# STM32f103RBT6.net
KiCad netlist of a schematic drawn in Altium Designer
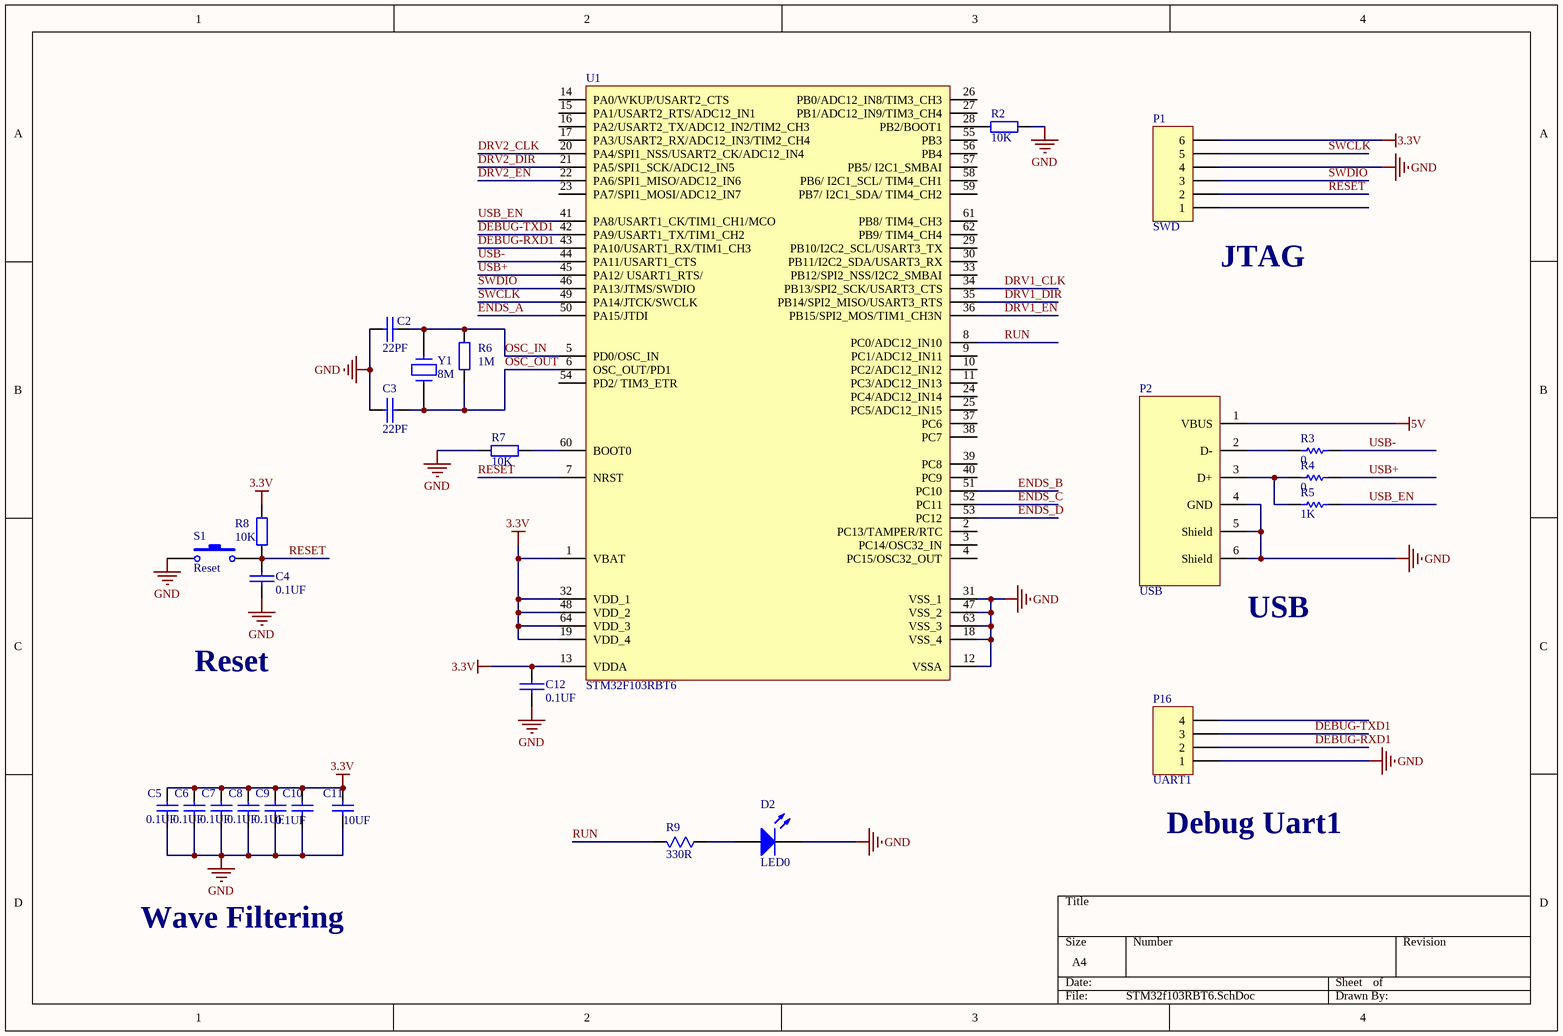
[diagram p0: STM32f103RBT6.SchDoc]

(export (version "E")
  (design (tool "Eeschema 10.0.6"))
  (components
    (comp (ref "C2")
      (value "22PF")
      (footprint "0603(1608)")
      (description "Capacitor")
      (libsource (lib "*") (part "CAP"))
    )
    (comp (ref "C3")
      (value "22PF")
      (footprint "0603(1608)")
      (description "Capacitor")
      (libsource (lib "*") (part "CAP"))
    )
    (comp (ref "C4")
      (value "0.1UF")
      (footprint "0603(1608)")
      (description "Capacitor")
      (libsource (lib "*") (part "CAP"))
    )
    (comp (ref "C5")
      (value "0.1UF")
      (footprint "0603(1608)")
      (description "Capacitor")
      (fields (field (name "PUBLISHER") "Altium Limited"))
      (libsource (lib "*") (part "Cap"))
    )
    (comp (ref "C6")
      (value "0.1UF")
      (footprint "0603(1608)")
      (description "Capacitor")
      (fields (field (name "PUBLISHER") "Altium Limited"))
      (libsource (lib "*") (part "Cap"))
    )
    (comp (ref "C7")
      (value "0.1UF")
      (footprint "0603(1608)")
      (description "Capacitor")
      (fields (field (name "PUBLISHER") "Altium Limited"))
      (libsource (lib "*") (part "Cap"))
    )
    (comp (ref "C8")
      (value "0.1UF")
      (footprint "0603(1608)")
      (description "Capacitor")
      (fields (field (name "PUBLISHER") "Altium Limited"))
      (libsource (lib "*") (part "Cap"))
    )
    (comp (ref "C9")
      (value "0.1UF")
      (footprint "0603(1608)")
      (description "Capacitor")
      (fields (field (name "PUBLISHER") "Altium Limited"))
      (libsource (lib "*") (part "Cap"))
    )
    (comp (ref "C10")
      (value "0.1UF")
      (footprint "0603(1608)")
      (description "Capacitor")
      (fields (field (name "PUBLISHER") "Altium Limited"))
      (libsource (lib "*") (part "Cap"))
    )
    (comp (ref "C11")
      (value "10UF")
      (footprint "0805(2012)")
      (description "Capacitor")
      (fields (field (name "PUBLISHER") "Altium Limited"))
      (libsource (lib "*") (part "Cap"))
    )
    (comp (ref "C12")
      (value "0.1UF")
      (footprint "0603(1608)")
      (description "Capacitor")
      (libsource (lib "*") (part "CAP"))
    )
    (comp (ref "D2")
      (value "LED0")
      (footprint "LED")
      (description "Typical INFRARED GaAs LED")
      (fields (field (name "PUBLISHER") "Altium Limited"))
      (libsource (lib "Miscellaneous Devices") (part "LED0"))
    )
    (comp (ref "P1")
      (value "SWD")
      (footprint "HDR1X6")
      (description "Header, 6-Pin")
      (fields (field (name "PUBLISHER") "Altium Limited"))
      (libsource (lib "Miscellaneous Connectors") (part "Header 6"))
    )
    (comp (ref "P2") (value "USB") (footprint "USB/SM0.8-6H5") (libsource (lib "Schlib_ZG") (part "Con Usb")))
    (comp (ref "P16")
      (value "UART1")
      (footprint "HDR1X4")
      (description "Header, 4-Pin")
      (fields (field (name "PUBLISHER") "Altium Limited"))
      (libsource (lib "Miscellaneous Connectors") (part "Header 4"))
    )
    (comp (ref "R2")
      (value "10K")
      (footprint "0603(1608)")
      (description "Resistor")
      (libsource (lib "Miscellaneous Devices") (part "Res2"))
    )
    (comp (ref "R3")
      (value "0")
      (footprint "0603(1608)")
      (description "Semiconductor Resistor")
      (fields (field (name "PUBLISHER") "Altium Limited"))
      (libsource (lib "Miscellaneous Devices") (part "Res Semi"))
    )
    (comp (ref "R4")
      (value "0")
      (footprint "0603(1608)")
      (description "Semiconductor Resistor")
      (fields (field (name "PUBLISHER") "Altium Limited"))
      (libsource (lib "Miscellaneous Devices") (part "Res Semi"))
    )
    (comp (ref "R5")
      (value "1K")
      (footprint "0603(1608)")
      (description "Semiconductor Resistor")
      (fields (field (name "PUBLISHER") "Altium Limited"))
      (libsource (lib "Miscellaneous Devices") (part "Res Semi"))
    )
    (comp (ref "R6")
      (value "1M")
      (footprint "0603(1608)")
      (description "Resistor")
      (libsource (lib "") (part "Res2_1"))
    )
    (comp (ref "R7")
      (value "10K")
      (footprint "0603(1608)")
      (description "Resistor")
      (libsource (lib "Miscellaneous Devices") (part "Res2"))
    )
    (comp (ref "R8")
      (value "10K")
      (footprint "0603(1608)")
      (description "Resistor")
      (libsource (lib "") (part "Res2_1"))
    )
    (comp (ref "R9") (value "330R") (footprint "0603(1608)") (libsource (lib "YT1_SCH_99SE") (part "RES")))
    (comp (ref "S1")
      (value "Reset")
      (footprint "SW-6")
      (description "Switch")
      (fields (field (name "PUBLISHER") "Altium Limited"))
      (libsource (lib "Schlib_ZG") (part "SW-PB"))
    )
    (comp (ref "U1")
      (value "STM32F103RBT6")
      (footprint "LQFP64_M")
      (libsource (lib "Schlib_ZG") (part "STM32F103RBT6"))
    )
    (comp (ref "Y1")
      (value "8M")
      (footprint "BCY-W2/E4.7")
      (description "Crystal")
      (libsource (lib "*") (part "CRYSTAL"))
    )
  )
  (nets
    (net (code "1") (name "/DEBUG-RXD1") (class "Default")
      (node (ref "P16") (pin "2") (pinfunction "2_2") (pintype "passive"))
      (node (ref "U1") (pin "43") (pinfunction "PA10/USART1_RX/TIM1_CH3_43") (pintype "passive"))
    )
    (net (code "2") (name "/DEBUG-TXD1") (class "Default")
      (node (ref "P16") (pin "3") (pinfunction "3_3") (pintype "passive"))
      (node (ref "U1") (pin "42") (pinfunction "PA9/USART1_TX/TIM1_CH2_42") (pintype "passive"))
    )
    (net (code "3") (name "/DRV1_CLK") (class "Default")
      (node (ref "U1") (pin "34") (pinfunction "PB13/SPI2_SCK/USART3_CTS_34") (pintype "passive"))
    )
    (net (code "4") (name "/DRV1_DIR") (class "Default")
      (node (ref "U1") (pin "35") (pinfunction "PB14/SPI2_MISO/USART3_RTS_35") (pintype "passive"))
    )
    (net (code "5") (name "/DRV1_EN") (class "Default")
      (node (ref "U1") (pin "36") (pinfunction "PB15/SPI2_MOS/TIM1_CH3N_36") (pintype "passive"))
    )
    (net (code "6") (name "/DRV2_CLK") (class "Default")
      (node (ref "U1") (pin "20") (pinfunction "PA4/SPI1_NSS/USART2_CK/ADC12_IN4_20") (pintype "passive"))
    )
    (net (code "7") (name "/DRV2_DIR") (class "Default")
      (node (ref "U1") (pin "21") (pinfunction "PA5/SPI1_SCK/ADC12_IN5_21") (pintype "passive"))
    )
    (net (code "8") (name "/DRV2_EN") (class "Default")
      (node (ref "U1") (pin "22") (pinfunction "PA6/SPI1_MISO/ADC12_IN6_22") (pintype "passive"))
    )
    (net (code "9") (name "/ENDS_A") (class "Default")
      (node (ref "U1") (pin "50") (pinfunction "PA15/JTDI_50") (pintype "passive"))
    )
    (net (code "10") (name "/ENDS_B") (class "Default")
      (node (ref "U1") (pin "51") (pinfunction "PC10_51") (pintype "passive"))
    )
    (net (code "11") (name "/ENDS_C") (class "Default")
      (node (ref "U1") (pin "52") (pinfunction "PC11_52") (pintype "passive"))
    )
    (net (code "12") (name "/ENDS_D") (class "Default")
      (node (ref "U1") (pin "53") (pinfunction "PC12_53") (pintype "passive"))
    )
    (net (code "13") (name "/OSC_IN") (class "Default")
      (node (ref "C2") (pin "2") (pinfunction "2_2") (pintype "passive"))
      (node (ref "R6") (pin "1") (pinfunction "1_1") (pintype "passive"))
      (node (ref "U1") (pin "5") (pinfunction "PD0/OSC_IN_5") (pintype "passive"))
      (node (ref "Y1") (pin "1") (pinfunction "1_1") (pintype "passive"))
    )
    (net (code "14") (name "/OSC_OUT") (class "Default")
      (node (ref "C3") (pin "1") (pinfunction "1_1") (pintype "passive"))
      (node (ref "R6") (pin "2") (pinfunction "2_2") (pintype "passive"))
      (node (ref "U1") (pin "6") (pinfunction "OSC_OUT/PD1_6") (pintype "passive"))
      (node (ref "Y1") (pin "2") (pinfunction "2_2") (pintype "passive"))
    )
    (net (code "15") (name "/RESET") (class "Default")
      (node (ref "C4") (pin "2") (pinfunction "2_2") (pintype "passive"))
      (node (ref "P1") (pin "2") (pinfunction "2_2") (pintype "passive"))
      (node (ref "R8") (pin "2") (pinfunction "2_2") (pintype "passive"))
      (node (ref "S1") (pin "2") (pinfunction "2_2") (pintype "passive"))
      (node (ref "U1") (pin "7") (pinfunction "NRST_7") (pintype "passive"))
    )
    (net (code "16") (name "/RUN") (class "Default")
      (node (ref "R9") (pin "2") (pinfunction "2_2") (pintype "passive"))
      (node (ref "U1") (pin "8") (pinfunction "PC0/ADC12_IN10_8") (pintype "passive"))
    )
    (net (code "17") (name "/SWCLK") (class "Default")
      (node (ref "P1") (pin "5") (pinfunction "5_5") (pintype "passive"))
      (node (ref "U1") (pin "49") (pinfunction "PA14/JTCK/SWCLK_49") (pintype "passive"))
    )
    (net (code "18") (name "/SWDIO") (class "Default")
      (node (ref "P1") (pin "3") (pinfunction "3_3") (pintype "passive"))
      (node (ref "U1") (pin "46") (pinfunction "PA13/JTMS/SWDIO_46") (pintype "passive"))
    )
    (net (code "19") (name "/USB+") (class "Default")
      (node (ref "R4") (pin "2") (pinfunction "2_2") (pintype "passive"))
      (node (ref "U1") (pin "45") (pinfunction "PA12/_USART1_RTS/_45") (pintype "passive"))
    )
    (net (code "20") (name "/USB-") (class "Default")
      (node (ref "R3") (pin "2") (pinfunction "2_2") (pintype "passive"))
      (node (ref "U1") (pin "44") (pinfunction "PA11/USART1_CTS_44") (pintype "passive"))
    )
    (net (code "21") (name "/USB_EN") (class "Default")
      (node (ref "R5") (pin "2") (pinfunction "2_2") (pintype "passive"))
      (node (ref "U1") (pin "41") (pinfunction "PA8/USART1_CK/TIM1_CH1/MCO_41") (pintype "passive"))
    )
    (net (code "22") (name "3.3V") (class "Default")
      (node (ref "C10") (pin "1") (pinfunction "1_1") (pintype "passive"))
      (node (ref "C11") (pin "1") (pinfunction "1_1") (pintype "passive"))
      (node (ref "C12") (pin "2") (pinfunction "2_2") (pintype "passive"))
      (node (ref "C5") (pin "1") (pinfunction "1_1") (pintype "passive"))
      (node (ref "C6") (pin "1") (pinfunction "1_1") (pintype "passive"))
      (node (ref "C7") (pin "1") (pinfunction "1_1") (pintype "passive"))
      (node (ref "C8") (pin "1") (pinfunction "1_1") (pintype "passive"))
      (node (ref "C9") (pin "1") (pinfunction "1_1") (pintype "passive"))
      (node (ref "P1") (pin "6") (pinfunction "6_6") (pintype "passive"))
      (node (ref "R8") (pin "1") (pinfunction "1_1") (pintype "passive"))
      (node (ref "U1") (pin "1") (pinfunction "VBAT_1") (pintype "passive"))
      (node (ref "U1") (pin "13") (pinfunction "VDDA_13") (pintype "passive"))
      (node (ref "U1") (pin "19") (pinfunction "VDD_4_19") (pintype "passive"))
      (node (ref "U1") (pin "32") (pinfunction "VDD_1_32") (pintype "passive"))
      (node (ref "U1") (pin "48") (pinfunction "VDD_2_48") (pintype "passive"))
      (node (ref "U1") (pin "64") (pinfunction "VDD_3_64") (pintype "passive"))
    )
    (net (code "23") (name "5V") (class "Default")
      (node (ref "P2") (pin "1") (pinfunction "VBUS_1") (pintype "power_in"))
    )
    (net (code "24") (name "GND") (class "Default")
      (node (ref "C10") (pin "2") (pinfunction "2_2") (pintype "passive"))
      (node (ref "C11") (pin "2") (pinfunction "2_2") (pintype "passive"))
      (node (ref "C12") (pin "1") (pinfunction "1_1") (pintype "passive"))
      (node (ref "C2") (pin "1") (pinfunction "1_1") (pintype "passive"))
      (node (ref "C3") (pin "2") (pinfunction "2_2") (pintype "passive"))
      (node (ref "C4") (pin "1") (pinfunction "1_1") (pintype "passive"))
      (node (ref "C5") (pin "2") (pinfunction "2_2") (pintype "passive"))
      (node (ref "C6") (pin "2") (pinfunction "2_2") (pintype "passive"))
      (node (ref "C7") (pin "2") (pinfunction "2_2") (pintype "passive"))
      (node (ref "C8") (pin "2") (pinfunction "2_2") (pintype "passive"))
      (node (ref "C9") (pin "2") (pinfunction "2_2") (pintype "passive"))
      (node (ref "D2") (pin "2") (pinfunction "K_2") (pintype "passive"))
      (node (ref "P1") (pin "4") (pinfunction "4_4") (pintype "passive"))
      (node (ref "P16") (pin "1") (pinfunction "1_1") (pintype "passive"))
      (node (ref "P2") (pin "4") (pinfunction "GND_4") (pintype "power_in"))
      (node (ref "P2") (pin "5") (pinfunction "Shield_5") (pintype "power_in"))
      (node (ref "P2") (pin "6") (pinfunction "Shield_6") (pintype "power_in"))
      (node (ref "R2") (pin "2") (pinfunction "2_2") (pintype "passive"))
      (node (ref "R7") (pin "1") (pinfunction "1_1") (pintype "passive"))
      (node (ref "S1") (pin "1") (pinfunction "1_1") (pintype "passive"))
      (node (ref "U1") (pin "12") (pinfunction "VSSA_12") (pintype "passive"))
      (node (ref "U1") (pin "18") (pinfunction "VSS_4_18") (pintype "passive"))
      (node (ref "U1") (pin "31") (pinfunction "VSS_1_31") (pintype "passive"))
      (node (ref "U1") (pin "47") (pinfunction "VSS_2_47") (pintype "passive"))
      (node (ref "U1") (pin "63") (pinfunction "VSS_3_63") (pintype "passive"))
    )
    (net (code "25") (name "Net-(D2-A)") (class "Default")
      (node (ref "D2") (pin "1") (pinfunction "A_1") (pintype "passive"))
      (node (ref "R9") (pin "1") (pinfunction "1_1") (pintype "passive"))
    )
    (net (code "26") (name "Net-(P2-D+)") (class "Default")
      (node (ref "P2") (pin "3") (pinfunction "D+_3") (pintype "power_in"))
      (node (ref "R4") (pin "1") (pinfunction "1_1") (pintype "passive"))
      (node (ref "R5") (pin "1") (pinfunction "1_1") (pintype "passive"))
    )
    (net (code "27") (name "Net-(P2-D-)") (class "Default")
      (node (ref "P2") (pin "2") (pinfunction "D-_2") (pintype "power_in"))
      (node (ref "R3") (pin "1") (pinfunction "1_1") (pintype "passive"))
    )
    (net (code "28") (name "Net-(U1-BOOT0)") (class "Default")
      (node (ref "R7") (pin "2") (pinfunction "2_2") (pintype "passive"))
      (node (ref "U1") (pin "60") (pinfunction "BOOT0_60") (pintype "passive"))
    )
    (net (code "29") (name "Net-(U1-PB2{slash}BOOT1)") (class "Default")
      (node (ref "R2") (pin "1") (pinfunction "1_1") (pintype "passive"))
      (node (ref "U1") (pin "28") (pinfunction "PB2/BOOT1_28") (pintype "passive"))
    )
    (net (code "30") (name "unconnected-(P1-Pad1)") (class "Default")
      (node (ref "P1") (pin "1") (pinfunction "1_1") (pintype "passive"))
    )
    (net (code "31") (name "unconnected-(P16-Pad4)") (class "Default")
      (node (ref "P16") (pin "4") (pinfunction "4_4") (pintype "passive"))
    )
    (net (code "32") (name "unconnected-(U1-PA0{slash}WKUP{slash}USART2_CTS-Pad14)") (class "Default")
      (node (ref "U1") (pin "14") (pinfunction "PA0/WKUP/USART2_CTS_14") (pintype "passive"))
    )
    (net (code "33") (name "unconnected-(U1-PA1{slash}USART2_RTS{slash}ADC12_IN1-Pad15)") (class "Default")
      (node (ref "U1") (pin "15") (pinfunction "PA1/USART2_RTS/ADC12_IN1_15") (pintype "passive"))
    )
    (net (code "34") (name "unconnected-(U1-PA2{slash}USART2_TX{slash}ADC12_IN2{slash}TIM2_CH3-Pad16)") (class "Default")
      (node (ref "U1") (pin "16") (pinfunction "PA2/USART2_TX/ADC12_IN2/TIM2_CH3_16") (pintype "passive"))
    )
    (net (code "35") (name "unconnected-(U1-PA3{slash}USART2_RX{slash}ADC12_IN3{slash}TIM2_CH4-Pad17)") (class "Default")
      (node (ref "U1") (pin "17") (pinfunction "PA3/USART2_RX/ADC12_IN3/TIM2_CH4_17") (pintype "passive"))
    )
    (net (code "36") (name "unconnected-(U1-PA7{slash}SPI1_MOSI{slash}ADC12_IN7-Pad23)") (class "Default")
      (node (ref "U1") (pin "23") (pinfunction "PA7/SPI1_MOSI/ADC12_IN7_23") (pintype "passive"))
    )
    (net (code "37") (name "unconnected-(U1-PB0{slash}ADC12_IN8{slash}TIM3_CH3-Pad26)") (class "Default")
      (node (ref "U1") (pin "26") (pinfunction "PB0/ADC12_IN8/TIM3_CH3_26") (pintype "passive"))
    )
    (net (code "38") (name "unconnected-(U1-PB1{slash}ADC12_IN9{slash}TIM3_CH4-Pad27)") (class "Default")
      (node (ref "U1") (pin "27") (pinfunction "PB1/ADC12_IN9/TIM3_CH4_27") (pintype "passive"))
    )
    (net (code "39") (name "unconnected-(U1-PB3-Pad55)") (class "Default")
      (node (ref "U1") (pin "55") (pinfunction "PB3_55") (pintype "passive"))
    )
    (net (code "40") (name "unconnected-(U1-PB4-Pad56)") (class "Default")
      (node (ref "U1") (pin "56") (pinfunction "PB4_56") (pintype "passive"))
    )
    (net (code "41") (name "unconnected-(U1-PB5{slash}_I2C1_SMBAI-Pad57)") (class "Default")
      (node (ref "U1") (pin "57") (pinfunction "PB5/_I2C1_SMBAI_57") (pintype "passive"))
    )
    (net (code "42") (name "unconnected-(U1-PB6{slash}_I2C1_SCL{slash}_TIM4_CH1-Pad58)") (class "Default")
      (node (ref "U1") (pin "58") (pinfunction "PB6/_I2C1_SCL/_TIM4_CH1_58") (pintype "passive"))
    )
    (net (code "43") (name "unconnected-(U1-PB7{slash}_I2C1_SDA{slash}_TIM4_CH2-Pad59)") (class "Default")
      (node (ref "U1") (pin "59") (pinfunction "PB7/_I2C1_SDA/_TIM4_CH2_59") (pintype "passive"))
    )
    (net (code "44") (name "unconnected-(U1-PB8{slash}_TIM4_CH3-Pad61)") (class "Default")
      (node (ref "U1") (pin "61") (pinfunction "PB8/_TIM4_CH3_61") (pintype "passive"))
    )
    (net (code "45") (name "unconnected-(U1-PB9{slash}_TIM4_CH4-Pad62)") (class "Default")
      (node (ref "U1") (pin "62") (pinfunction "PB9/_TIM4_CH4_62") (pintype "passive"))
    )
    (net (code "46") (name "unconnected-(U1-PB10{slash}I2C2_SCL{slash}USART3_TX-Pad29)") (class "Default")
      (node (ref "U1") (pin "29") (pinfunction "PB10/I2C2_SCL/USART3_TX_29") (pintype "passive"))
    )
    (net (code "47") (name "unconnected-(U1-PB11{slash}I2C2_SDA{slash}USART3_RX-Pad30)") (class "Default")
      (node (ref "U1") (pin "30") (pinfunction "PB11/I2C2_SDA/USART3_RX_30") (pintype "passive"))
    )
    (net (code "48") (name "unconnected-(U1-PB12{slash}SPI2_NSS{slash}I2C2_SMBAI-Pad33)") (class "Default")
      (node (ref "U1") (pin "33") (pinfunction "PB12/SPI2_NSS/I2C2_SMBAI_33") (pintype "passive"))
    )
    (net (code "49") (name "unconnected-(U1-PC1{slash}ADC12_IN11-Pad9)") (class "Default")
      (node (ref "U1") (pin "9") (pinfunction "PC1/ADC12_IN11_9") (pintype "passive"))
    )
    (net (code "50") (name "unconnected-(U1-PC2{slash}ADC12_IN12-Pad10)") (class "Default")
      (node (ref "U1") (pin "10") (pinfunction "PC2/ADC12_IN12_10") (pintype "passive"))
    )
    (net (code "51") (name "unconnected-(U1-PC3{slash}ADC12_IN13-Pad11)") (class "Default")
      (node (ref "U1") (pin "11") (pinfunction "PC3/ADC12_IN13_11") (pintype "passive"))
    )
    (net (code "52") (name "unconnected-(U1-PC4{slash}ADC12_IN14-Pad24)") (class "Default")
      (node (ref "U1") (pin "24") (pinfunction "PC4/ADC12_IN14_24") (pintype "passive"))
    )
    (net (code "53") (name "unconnected-(U1-PC5{slash}ADC12_IN15-Pad25)") (class "Default")
      (node (ref "U1") (pin "25") (pinfunction "PC5/ADC12_IN15_25") (pintype "passive"))
    )
    (net (code "54") (name "unconnected-(U1-PC6-Pad37)") (class "Default")
      (node (ref "U1") (pin "37") (pinfunction "PC6_37") (pintype "passive"))
    )
    (net (code "55") (name "unconnected-(U1-PC7-Pad38)") (class "Default")
      (node (ref "U1") (pin "38") (pinfunction "PC7_38") (pintype "passive"))
    )
    (net (code "56") (name "unconnected-(U1-PC8-Pad39)") (class "Default")
      (node (ref "U1") (pin "39") (pinfunction "PC8_39") (pintype "passive"))
    )
    (net (code "57") (name "unconnected-(U1-PC9-Pad40)") (class "Default")
      (node (ref "U1") (pin "40") (pinfunction "PC9_40") (pintype "passive"))
    )
    (net (code "58") (name "unconnected-(U1-PC13{slash}TAMPER{slash}RTC-Pad2)") (class "Default")
      (node (ref "U1") (pin "2") (pinfunction "PC13/TAMPER/RTC_2") (pintype "passive"))
    )
    (net (code "59") (name "unconnected-(U1-PC14{slash}OSC32_IN-Pad3)") (class "Default")
      (node (ref "U1") (pin "3") (pinfunction "PC14/OSC32_IN_3") (pintype "passive"))
    )
    (net (code "60") (name "unconnected-(U1-PC15{slash}OSC32_OUT-Pad4)") (class "Default")
      (node (ref "U1") (pin "4") (pinfunction "PC15/OSC32_OUT_4") (pintype "passive"))
    )
    (net (code "61") (name "unconnected-(U1-PD2{slash}_TIM3_ETR-Pad54)") (class "Default")
      (node (ref "U1") (pin "54") (pinfunction "PD2/_TIM3_ETR_54") (pintype "passive"))
    )
  )
)
